# power-input.net
KiCad netlist of a schematic drawn in Altium Designer
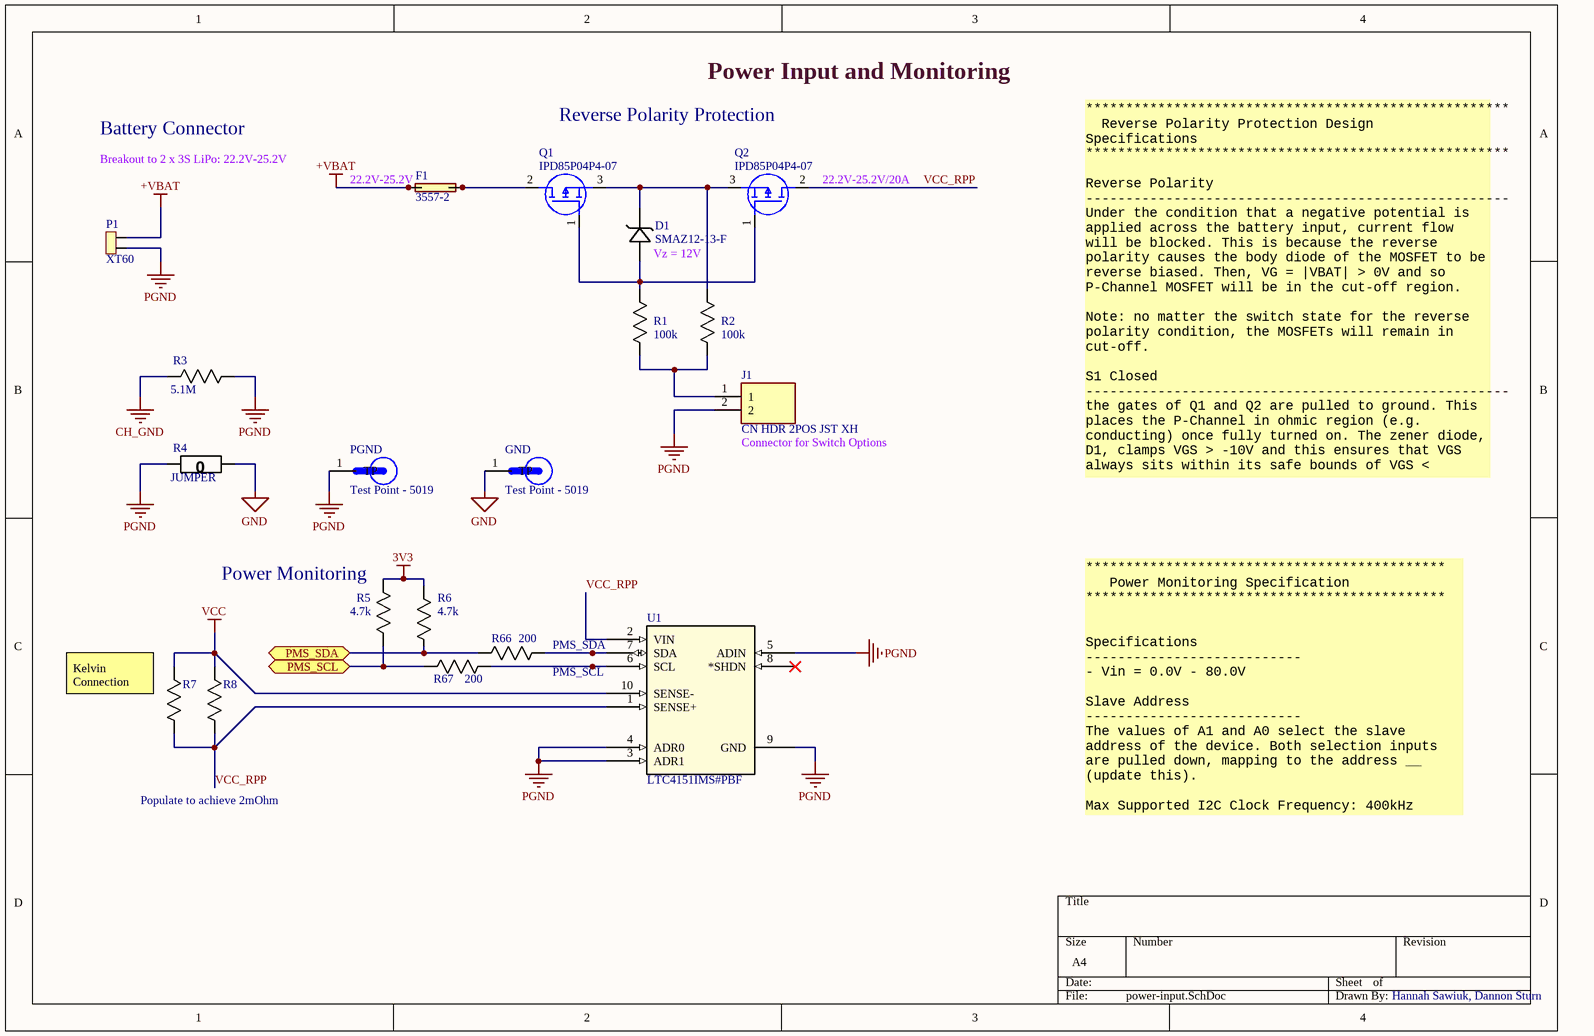
[diagram p0: power-input.SchDoc]

(export (version "E")
  (design (tool "Eeschema 10.0.6"))
  (components
    (comp (ref "D1")
      (value "SMAZ12-13-F")
      (footprint "SMA_DIO-L")
      (description "Zener Diode 12 V 1 W ±5% Surface Mount SMA")
      (fields
        (field (name "PART NUMBER") "DIODE ZENER 12V 1W")
        (field (name "COPYRIGHT") "Copyright (C) 2021 Ultra Librarian. All rights reserved.")
      )
      (libsource (lib "Diode_Library") (part "DIODE ZENER 12V 1W"))
    )
    (comp (ref "F1")
      (value "3557-2")
      (footprint "FUSE-3549-2")
      (description "Fuse Block 30A 500V 1 Circuit Blade Through Hole")
      (fields (field (name "MF") "Keystone Electronics") (field (name "PART NUMBER") "FUSE BLADE"))
      (libsource (lib "Fuse_Library") (part "FUSE BLADE"))
    )
    (comp (ref "GND")
      (value "Test Point - 5019")
      (footprint "TP380X203")
      (description "PC Test Point, Miniature Phosphor Bronze, Silver Plating Surface Mount Mounting Type")
      (fields (field (name "MP") "5019") (field (name "MF") "Keystone Electronics"))
      (libsource (lib "IC_Library") (part "Test Point - 5019"))
    )
    (comp (ref "J1")
      (value "CN HDR 2POS JST XH")
      (footprint "JST_S2B-XH-A(LF)(SN)")
      (description "Connector Header Through Hole 2 position 0.098 _2.50mm_\r\nJST XH")
      (fields (field (name "MP") "B2B-XH-A_LF__SN_") (field (name "MF") "JST Sales"))
      (libsource (lib "Connector_Library") (part "CN HDR 2POS JST XH"))
    )
    (comp (ref "P1")
      (value "XT60")
      (footprint "Amass_XT60PW-M")
      (description "XT60 CONNECTORS FEMALE PAIR")
      (fields (field (name "MF") "SparkFun Electronics") (field (name "MP") "PRT-10474"))
      (libsource (lib "Connector_Library") (part "XT60 Connector"))
    )
    (comp (ref "PGND")
      (value "Test Point - 5019")
      (footprint "TP380X203")
      (description "PC Test Point, Miniature Phosphor Bronze, Silver Plating Surface Mount Mounting Type")
      (fields (field (name "MP") "5019") (field (name "MF") "Keystone Electronics"))
      (libsource (lib "IC_Library") (part "Test Point - 5019"))
    )
    (comp (ref "PMS_SCL")
      (value "Test Point (Via)")
      (footprint "TP")
      (libsource (lib "IC_Library") (part "Test Point (Via)"))
    )
    (comp (ref "PMS_SDA")
      (value "Test Point (Via)")
      (footprint "TP")
      (libsource (lib "IC_Library") (part "Test Point (Via)"))
    )
    (comp (ref "Q1")
      (value "IPD85P04P4-07")
      (footprint "DPAK (TO-252)")
      (description "P-Channel 40 V 85A (Tc) 88W (Tc) Surface Mount PG-TO252-3-313")
      (fields (field (name "PART NUMBER") "MOSFET IPD85P04P4-07"))
      (libsource (lib "Transistor_Library") (part "MOSFET IPD85P04P4-07"))
    )
    (comp (ref "Q2")
      (value "IPD85P04P4-07")
      (footprint "DPAK (TO-252)")
      (description "P-Channel 40 V 85A (Tc) 88W (Tc) Surface Mount PG-TO252-3-313")
      (fields (field (name "PART NUMBER") "MOSFET IPD85P04P4-07"))
      (libsource (lib "Transistor_Library") (part "MOSFET IPD85P04P4-07"))
    )
    (comp (ref "R1")
      (value "100k")
      (footprint "0603")
      (description "RES SMD 100K OHM 1% 1/8W 0603")
      (fields (field (name "TOLERANCE") "1%") (field (name "PART NUMBER") "RES 100k 1/8W - 1%"))
      (libsource (lib "Resistor_Library") (part "RES 100k 1/8W 1%"))
    )
    (comp (ref "R2")
      (value "100k")
      (footprint "0603")
      (description "RES SMD 100K OHM 1% 1/8W 0603")
      (fields (field (name "TOLERANCE") "1%") (field (name "PART NUMBER") "RES 100k 1/8W - 1%"))
      (libsource (lib "Resistor_Library") (part "RES 100k 1/8W 1%"))
    )
    (comp (ref "R3")
      (value "5.1M")
      (footprint "0603")
      (description "RES SMD 5.1 MOHM 5% 1/8W 0603")
      (fields (field (name "TOLERANCE") "5%") (field (name "PART NUMBER") "RES 5.1M 1/8W-5%"))
      (libsource (lib "Resistor_Library") (part "RES 5.1M 1/8W-5%"))
    )
    (comp (ref "R4")
      (value "JUMPER")
      (footprint "1210")
      (description "RES SMD 0 OHM JUMPER GENERIC 0603")
      (fields (field (name "PART NUMBER") "RES 0 JUMPER"))
      (libsource (lib "Resistor_Library") (part "RES 0 JUMPER"))
    )
    (comp (ref "R5")
      (value "4.7k")
      (footprint "0603")
      (description "RES SMD 4.7k OHM 5% 1/8W 0603")
      (fields (field (name "TOLERANCE") "5%") (field (name "PART NUMBER") "RES 4.7k 1/8W - 5%"))
      (libsource (lib "Resistor_Library") (part "RES 4.7k 1/8W - 5%"))
    )
    (comp (ref "R6")
      (value "4.7k")
      (footprint "0603")
      (description "RES SMD 4.7k OHM 5% 1/8W 0603")
      (fields (field (name "TOLERANCE") "5%") (field (name "PART NUMBER") "RES 4.7k 1/8W - 5%"))
      (libsource (lib "") (part "RES 4.7k 1/8W - 5%_1"))
    )
    (comp (ref "R7")
      (value "2mOHM")
      (footprint "2512")
      (description "RES SMD 2m OHM 1% 1W 2512")
      (fields (field (name "TOLERANCE") "1%") (field (name "PART NUMBER") "RES 2m 1W"))
      (libsource (lib "Resistor_Library") (part "RES 2m 1W"))
    )
    (comp (ref "R8")
      (value "2mOHM")
      (footprint "2512")
      (description "RES SMD 2m OHM 1% 1W 2512")
      (fields (field (name "TOLERANCE") "1%") (field (name "PART NUMBER") "RES 2m 1W"))
      (libsource (lib "Resistor_Library") (part "RES 2m 1W"))
    )
    (comp (ref "R66")
      (value "200")
      (footprint "0603")
      (description "RES SMD 200 OHM 5% 1/8W 0603")
      (fields (field (name "TOLERANCE") "5%") (field (name "PART NUMBER") "RES 200.0 1/8W"))
      (libsource (lib "Resistor_Library") (part "RES 200.0 1/8W"))
    )
    (comp (ref "R67")
      (value "200")
      (footprint "0603")
      (description "RES SMD 200 OHM 5% 1/8W 0603")
      (fields (field (name "TOLERANCE") "5%") (field (name "PART NUMBER") "RES 200.0 1/8W"))
      (libsource (lib "Resistor_Library") (part "RES 200.0 1/8W"))
    )
    (comp (ref "U1")
      (value "LTC4151IMS#PBF")
      (footprint "MSOP-10_MS_LIT")
      (description "IC CURRENT MONITOR(12BIT) 10MSOP")
      (fields
        (field (name "MANUFACTURER_PART_NUMBER") "ltc4151ims#pbf")
        (field (name "COPYRIGHT") "Copyright (C) 2021 Ultra Librarian. All rights reserved.")
      )
      (libsource (lib "IC_Library") (part "ltc4151ims#pbf"))
    )
  )
  (nets
    (net (code "1") (name "+VBAT") (class "Default")
      (node (ref "F1") (pin "3") (pinfunction "2A_3") (pintype "passive"))
      (node (ref "F1") (pin "4") (pinfunction "2B_4") (pintype "passive"))
      (node (ref "P1") (pin "2") (pinfunction "2_2") (pintype "passive"))
    )
    (net (code "2") (name "/PMS_SCL") (class "Default")
      (node (ref "R5") (pin "1") (pinfunction "R1_1") (pintype "passive"))
      (node (ref "R67") (pin "2") (pinfunction "R2_2") (pintype "passive"))
    )
    (net (code "3") (name "/PMS_SDA") (class "Default")
      (node (ref "R6") (pin "1") (pinfunction "R1_1") (pintype "passive"))
      (node (ref "R66") (pin "2") (pinfunction "R2_2") (pintype "passive"))
    )
    (net (code "4") (name "/VCC_RPP") (class "Default")
      (node (ref "Q2") (pin "2") (pinfunction "D_2") (pintype "passive"))
      (node (ref "R7") (pin "2") (pinfunction "R2_2") (pintype "passive"))
      (node (ref "R8") (pin "2") (pinfunction "R2_2") (pintype "passive"))
      (node (ref "U1") (pin "1") (pinfunction "SENSE+_1") (pintype "input"))
      (node (ref "U1") (pin "2") (pinfunction "VIN_2") (pintype "input"))
    )
    (net (code "5") (name "3V3") (class "Default")
      (node (ref "R5") (pin "2") (pinfunction "R2_2") (pintype "passive"))
      (node (ref "R6") (pin "2") (pinfunction "R2_2") (pintype "passive"))
    )
    (net (code "6") (name "CH_GND") (class "Default")
      (node (ref "R3") (pin "2") (pinfunction "R2_2") (pintype "passive"))
    )
    (net (code "7") (name "GND") (class "Default")
      (node (ref "GND") (pin "1") (pinfunction "TP_1") (pintype "passive"))
      (node (ref "R4") (pin "1") (pinfunction "R1_1") (pintype "passive"))
    )
    (net (code "8") (name "Net-(F1-1A)") (class "Default")
      (node (ref "F1") (pin "1") (pinfunction "1A_1") (pintype "passive"))
      (node (ref "F1") (pin "2") (pinfunction "1B_2") (pintype "passive"))
      (node (ref "Q1") (pin "2") (pinfunction "D_2") (pintype "passive"))
    )
    (net (code "9") (name "Net-(Q1-G)") (class "Default")
      (node (ref "D1") (pin "2") (pinfunction "2_2") (pintype "passive"))
      (node (ref "Q1") (pin "1") (pinfunction "G_1") (pintype "passive"))
      (node (ref "Q2") (pin "1") (pinfunction "G_1") (pintype "passive"))
      (node (ref "R1") (pin "1") (pinfunction "R1_1") (pintype "passive"))
    )
    (net (code "10") (name "Net-(Q1-S)") (class "Default")
      (node (ref "D1") (pin "1") (pinfunction "1_1") (pintype "passive"))
      (node (ref "Q1") (pin "3") (pinfunction "S_3") (pintype "passive"))
      (node (ref "Q2") (pin "3") (pinfunction "S_3") (pintype "passive"))
      (node (ref "R2") (pin "1") (pinfunction "R1_1") (pintype "passive"))
    )
    (net (code "11") (name "Net-(R1-R2)") (class "Default")
      (node (ref "J1") (pin "1") (pinfunction "1_1") (pintype "passive"))
      (node (ref "R1") (pin "2") (pinfunction "R2_2") (pintype "passive"))
      (node (ref "R2") (pin "2") (pinfunction "R2_2") (pintype "passive"))
    )
    (net (code "12") (name "Net-(R66-R1)") (class "Default")
      (node (ref "PMS_SDA") (pin "1") (pinfunction "1_1") (pintype "passive"))
      (node (ref "R66") (pin "1") (pinfunction "R1_1") (pintype "passive"))
      (node (ref "U1") (pin "7") (pinfunction "SDA_7") (pintype "bidirectional"))
    )
    (net (code "13") (name "Net-(R67-R1)") (class "Default")
      (node (ref "PMS_SCL") (pin "1") (pinfunction "1_1") (pintype "passive"))
      (node (ref "R67") (pin "1") (pinfunction "R1_1") (pintype "passive"))
      (node (ref "U1") (pin "6") (pinfunction "SCL_6") (pintype "input"))
    )
    (net (code "14") (name "PGND") (class "Default")
      (node (ref "J1") (pin "2") (pinfunction "2_2") (pintype "passive"))
      (node (ref "P1") (pin "1") (pinfunction "1_1") (pintype "passive"))
      (node (ref "PGND") (pin "1") (pinfunction "TP_1") (pintype "passive"))
      (node (ref "R3") (pin "1") (pinfunction "R1_1") (pintype "passive"))
      (node (ref "R4") (pin "2") (pinfunction "R2_2") (pintype "passive"))
      (node (ref "U1") (pin "3") (pinfunction "ADR1_3") (pintype "input"))
      (node (ref "U1") (pin "4") (pinfunction "ADR0_4") (pintype "input"))
      (node (ref "U1") (pin "5") (pinfunction "ADIN_5") (pintype "input"))
      (node (ref "U1") (pin "9") (pinfunction "GND_9") (pintype "power_in"))
    )
    (net (code "15") (name "VCC") (class "Default")
      (node (ref "R7") (pin "1") (pinfunction "R1_1") (pintype "passive"))
      (node (ref "R8") (pin "1") (pinfunction "R1_1") (pintype "passive"))
      (node (ref "U1") (pin "10") (pinfunction "SENSE-_10") (pintype "input"))
    )
    (net (code "16") (name "unconnected-(U1-*SHDN-Pad8)") (class "Default")
      (node (ref "U1") (pin "8") (pinfunction "*SHDN_8") (pintype "input+no_connect"))
    )
  )
)
